# Arduino_UART_SIDEWAYS.net
KiCad netlist of a schematic drawn in EAGLE
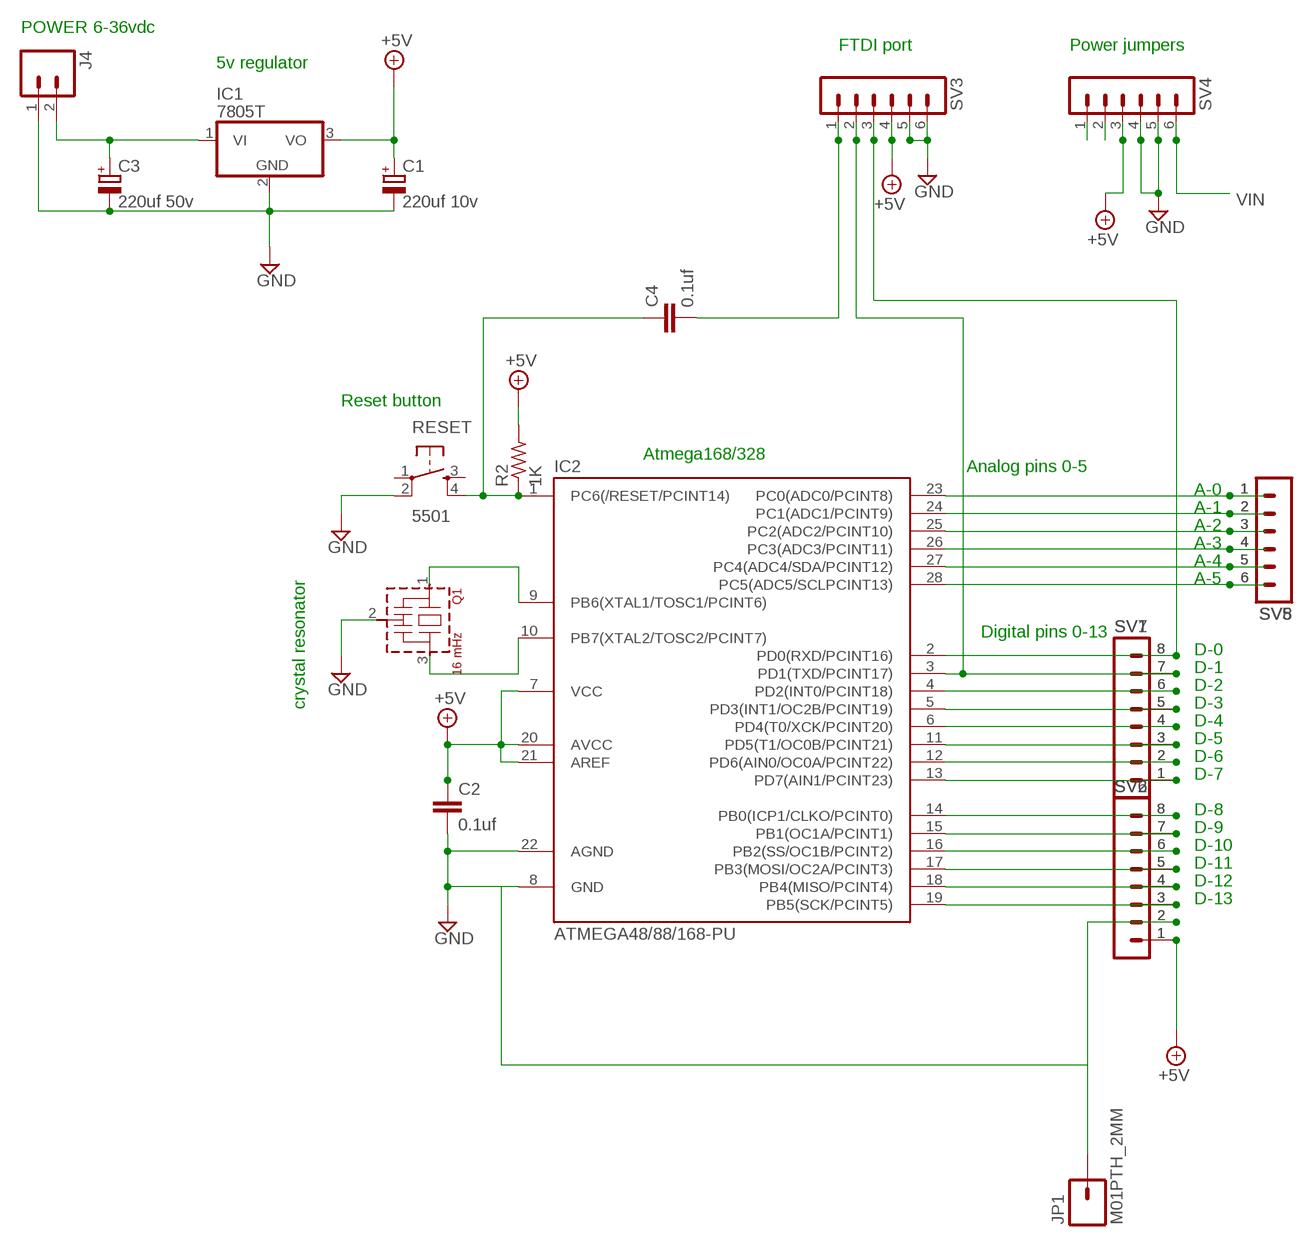
[diagram p0: schematic, sheet 1]

(export (version "E")
  (design (tool "Eeschema 10.0.6"))
  (components
    (comp (ref "C1")
      (value "220uf 10v")
      (footprint "eagle-import:E2,5-6")
      (libsource (lib "eagle-import") (part "CPOL-EUE2.5-6"))
    )
    (comp (ref "C2")
      (value "0.1uf")
      (footprint "eagle-import:C050-024X044")
      (libsource (lib "eagle-import") (part "C-EU050-024X044"))
    )
    (comp (ref "C3")
      (value "220uf 50v")
      (footprint "eagle-import:E2,5-6")
      (libsource (lib "eagle-import") (part "CPOL-EUE2.5-6"))
    )
    (comp (ref "C4")
      (value "0.1uf")
      (footprint "eagle-import:C075-032X103")
      (libsource (lib "eagle-import") (part "C-EU075-032X103"))
    )
    (comp (ref "IC1")
      (value "7805T")
      (footprint "eagle-import:TO220H")
      (libsource (lib "eagle-import") (part "78T05"))
    )
    (comp (ref "IC2")
      (value "ATMEGA48/88/168-PU")
      (footprint "eagle-import:DIL28-3")
      (libsource (lib "eagle-import") (part "ATMEGA48/88/168-PU"))
    )
    (comp (ref "J4")
      (value "M02LOCK")
      (footprint "eagle-import:1X02_LOCK")
      (libsource (lib "eagle-import") (part "M02LOCK"))
    )
    (comp (ref "JP1")
      (value "M01PTH_2MM")
      (footprint "eagle-import:1X01_2MM")
      (libsource (lib "eagle-import") (part "M01PTH_2MM"))
    )
    (comp (ref "Q1")
      (value "16 mHz")
      (footprint "eagle-import:CSTLS_X")
      (libsource (lib "eagle-import") (part "CSTLS_X"))
    )
    (comp (ref "R2")
      (value "1K")
      (footprint "eagle-import:0204_7")
      (libsource (lib "eagle-import") (part "R-US_0204/7"))
    )
    (comp (ref "RESET")
      (value "5501")
      (footprint "eagle-import:TACTILE-PTH")
      (libsource (lib "eagle-import") (part "TAC_SWITCHPTH"))
    )
    (comp (ref "SV1")
      (value "MA08-1")
      (footprint "eagle-import:MA08-1")
      (libsource (lib "eagle-import") (part "MA08-1"))
    )
    (comp (ref "SV2")
      (value "MA08-1")
      (footprint "eagle-import:MA08-1")
      (libsource (lib "eagle-import") (part "MA08-1"))
    )
    (comp (ref "SV3")
      (value "MA06-1")
      (footprint "eagle-import:MA06-1")
      (libsource (lib "eagle-import") (part "MA06-1"))
    )
    (comp (ref "SV4")
      (value "MA06-1")
      (footprint "eagle-import:MA06-1")
      (libsource (lib "eagle-import") (part "MA06-1"))
    )
    (comp (ref "SV5")
      (value "MA06-1")
      (footprint "eagle-import:MA06-1")
      (libsource (lib "eagle-import") (part "MA06-1"))
    )
    (comp (ref "SV6")
      (value "MA08-1")
      (footprint "eagle-import:MA08-1")
      (libsource (lib "eagle-import") (part "MA08-1"))
    )
    (comp (ref "SV7")
      (value "MA08-1")
      (footprint "eagle-import:MA08-1")
      (libsource (lib "eagle-import") (part "MA08-1"))
    )
    (comp (ref "SV8")
      (value "MA06-1")
      (footprint "eagle-import:MA06-1")
      (libsource (lib "eagle-import") (part "MA06-1"))
    )
  )
  (nets
    (net (code "1") (name "+5V") (class "Default")
      (node (ref "C1") (pin "+") (pinfunction "+_+") (pintype "passive"))
      (node (ref "C2") (pin "1") (pinfunction "1_1") (pintype "passive"))
      (node (ref "IC1") (pin "3") (pinfunction "VO_3") (pintype "passive"))
      (node (ref "IC2") (pin "20") (pinfunction "AVCC_20") (pintype "passive"))
      (node (ref "IC2") (pin "21") (pinfunction "AREF_21") (pintype "passive"))
      (node (ref "IC2") (pin "7") (pinfunction "VCC_7") (pintype "power_in"))
      (node (ref "R2") (pin "2") (pinfunction "2_2") (pintype "passive"))
      (node (ref "SV2") (pin "1") (pinfunction "1_1") (pintype "passive"))
      (node (ref "SV3") (pin "4") (pinfunction "4_4") (pintype "passive"))
      (node (ref "SV4") (pin "3") (pinfunction "3_3") (pintype "passive"))
      (node (ref "SV6") (pin "1") (pinfunction "1_1") (pintype "passive"))
    )
    (net (code "2") (name "/VIN") (class "Default")
      (node (ref "C3") (pin "+") (pinfunction "+_+") (pintype "passive"))
      (node (ref "IC1") (pin "1") (pinfunction "VI_1") (pintype "input"))
      (node (ref "J4") (pin "2") (pinfunction "2_2") (pintype "passive"))
      (node (ref "SV4") (pin "6") (pinfunction "6_6") (pintype "passive"))
    )
    (net (code "3") (name "GND") (class "Default")
      (node (ref "C1") (pin "-") (pinfunction "-_-") (pintype "passive"))
      (node (ref "C2") (pin "2") (pinfunction "2_2") (pintype "passive"))
      (node (ref "C3") (pin "-") (pinfunction "-_-") (pintype "passive"))
      (node (ref "IC1") (pin "2") (pinfunction "GND_2") (pintype "passive"))
      (node (ref "IC2") (pin "22") (pinfunction "AGND_22") (pintype "power_in"))
      (node (ref "IC2") (pin "8") (pinfunction "GND_8") (pintype "power_in"))
      (node (ref "J4") (pin "1") (pinfunction "1_1") (pintype "passive"))
      (node (ref "JP1") (pin "1") (pinfunction "1_1") (pintype "passive"))
      (node (ref "Q1") (pin "2") (pinfunction "VSS_2") (pintype "power_in"))
      (node (ref "RESET") (pin "2") (pinfunction "2_2") (pintype "passive"))
      (node (ref "SV2") (pin "2") (pinfunction "2_2") (pintype "passive"))
      (node (ref "SV3") (pin "5") (pinfunction "5_5") (pintype "passive"))
      (node (ref "SV3") (pin "6") (pinfunction "6_6") (pintype "passive"))
      (node (ref "SV4") (pin "4") (pinfunction "4_4") (pintype "passive"))
      (node (ref "SV4") (pin "5") (pinfunction "5_5") (pintype "passive"))
      (node (ref "SV6") (pin "2") (pinfunction "2_2") (pintype "passive"))
    )
    (net (code "4") (name "Net-(C4-Pad2)") (class "Default")
      (node (ref "C4") (pin "2") (pinfunction "2_2") (pintype "passive"))
      (node (ref "SV3") (pin "1") (pinfunction "1_1") (pintype "passive"))
    )
    (net (code "5") (name "Net-(IC2-PB0(ICP1{slash}CLKO{slash}PCINT0))") (class "Default")
      (node (ref "IC2") (pin "14") (pinfunction "PB0(ICP1/CLKO/PCINT0)_14") (pintype "bidirectional"))
      (node (ref "SV2") (pin "8") (pinfunction "8_8") (pintype "passive"))
      (node (ref "SV6") (pin "8") (pinfunction "8_8") (pintype "passive"))
    )
    (net (code "6") (name "Net-(IC2-PB1(OC1A{slash}PCINT1))") (class "Default")
      (node (ref "IC2") (pin "15") (pinfunction "PB1(OC1A/PCINT1)_15") (pintype "bidirectional"))
      (node (ref "SV2") (pin "7") (pinfunction "7_7") (pintype "passive"))
      (node (ref "SV6") (pin "7") (pinfunction "7_7") (pintype "passive"))
    )
    (net (code "7") (name "Net-(IC2-PB2(SS{slash}OC1B{slash}PCINT2))") (class "Default")
      (node (ref "IC2") (pin "16") (pinfunction "PB2(SS/OC1B/PCINT2)_16") (pintype "bidirectional"))
      (node (ref "SV2") (pin "6") (pinfunction "6_6") (pintype "passive"))
      (node (ref "SV6") (pin "6") (pinfunction "6_6") (pintype "passive"))
    )
    (net (code "8") (name "Net-(IC2-PB3(MOSI{slash}OC2A{slash}PCINT3))") (class "Default")
      (node (ref "IC2") (pin "17") (pinfunction "PB3(MOSI/OC2A/PCINT3)_17") (pintype "bidirectional"))
      (node (ref "SV2") (pin "5") (pinfunction "5_5") (pintype "passive"))
      (node (ref "SV6") (pin "5") (pinfunction "5_5") (pintype "passive"))
    )
    (net (code "9") (name "Net-(IC2-PB4(MISO{slash}PCINT4))") (class "Default")
      (node (ref "IC2") (pin "18") (pinfunction "PB4(MISO/PCINT4)_18") (pintype "bidirectional"))
      (node (ref "SV2") (pin "4") (pinfunction "4_4") (pintype "passive"))
      (node (ref "SV6") (pin "4") (pinfunction "4_4") (pintype "passive"))
    )
    (net (code "10") (name "Net-(IC2-PB5(SCK{slash}PCINT5))") (class "Default")
      (node (ref "IC2") (pin "19") (pinfunction "PB5(SCK/PCINT5)_19") (pintype "bidirectional"))
      (node (ref "SV2") (pin "3") (pinfunction "3_3") (pintype "passive"))
      (node (ref "SV6") (pin "3") (pinfunction "3_3") (pintype "passive"))
    )
    (net (code "11") (name "Net-(IC2-PB6(XTAL1{slash}TOSC1{slash}PCINT6))") (class "Default")
      (node (ref "IC2") (pin "9") (pinfunction "PB6(XTAL1/TOSC1/PCINT6)_9") (pintype "bidirectional"))
      (node (ref "Q1") (pin "1") (pinfunction "1_1") (pintype "output"))
    )
    (net (code "12") (name "Net-(IC2-PB7(XTAL2{slash}TOSC2{slash}PCINT7))") (class "Default")
      (node (ref "IC2") (pin "10") (pinfunction "PB7(XTAL2/TOSC2/PCINT7)_10") (pintype "bidirectional"))
      (node (ref "Q1") (pin "3") (pinfunction "3_3") (pintype "input"))
    )
    (net (code "13") (name "Net-(IC2-PC0(ADC0{slash}PCINT8))") (class "Default")
      (node (ref "IC2") (pin "23") (pinfunction "PC0(ADC0/PCINT8)_23") (pintype "bidirectional"))
      (node (ref "SV5") (pin "1") (pinfunction "1_1") (pintype "passive"))
      (node (ref "SV8") (pin "1") (pinfunction "1_1") (pintype "passive"))
    )
    (net (code "14") (name "Net-(IC2-PC1(ADC1{slash}PCINT9))") (class "Default")
      (node (ref "IC2") (pin "24") (pinfunction "PC1(ADC1/PCINT9)_24") (pintype "bidirectional"))
      (node (ref "SV5") (pin "2") (pinfunction "2_2") (pintype "passive"))
      (node (ref "SV8") (pin "2") (pinfunction "2_2") (pintype "passive"))
    )
    (net (code "15") (name "Net-(IC2-PC2(ADC2{slash}PCINT10))") (class "Default")
      (node (ref "IC2") (pin "25") (pinfunction "PC2(ADC2/PCINT10)_25") (pintype "bidirectional"))
      (node (ref "SV5") (pin "3") (pinfunction "3_3") (pintype "passive"))
      (node (ref "SV8") (pin "3") (pinfunction "3_3") (pintype "passive"))
    )
    (net (code "16") (name "Net-(IC2-PC3(ADC3{slash}PCINT11))") (class "Default")
      (node (ref "IC2") (pin "26") (pinfunction "PC3(ADC3/PCINT11)_26") (pintype "bidirectional"))
      (node (ref "SV5") (pin "4") (pinfunction "4_4") (pintype "passive"))
      (node (ref "SV8") (pin "4") (pinfunction "4_4") (pintype "passive"))
    )
    (net (code "17") (name "Net-(IC2-PC4(ADC4{slash}SDA{slash}PCINT12))") (class "Default")
      (node (ref "IC2") (pin "27") (pinfunction "PC4(ADC4/SDA/PCINT12)_27") (pintype "bidirectional"))
      (node (ref "SV5") (pin "5") (pinfunction "5_5") (pintype "passive"))
      (node (ref "SV8") (pin "5") (pinfunction "5_5") (pintype "passive"))
    )
    (net (code "18") (name "Net-(IC2-PC5(ADC5{slash}SCLPCINT13))") (class "Default")
      (node (ref "IC2") (pin "28") (pinfunction "PC5(ADC5/SCLPCINT13)_28") (pintype "bidirectional"))
      (node (ref "SV5") (pin "6") (pinfunction "6_6") (pintype "passive"))
      (node (ref "SV8") (pin "6") (pinfunction "6_6") (pintype "passive"))
    )
    (net (code "19") (name "Net-(IC2-PC6({slash}RESET{slash}PCINT14))") (class "Default")
      (node (ref "C4") (pin "1") (pinfunction "1_1") (pintype "passive"))
      (node (ref "IC2") (pin "1") (pinfunction "PC6(/RESET/PCINT14)_1") (pintype "bidirectional"))
      (node (ref "R2") (pin "1") (pinfunction "1_1") (pintype "passive"))
      (node (ref "RESET") (pin "4") (pinfunction "4_4") (pintype "passive"))
    )
    (net (code "20") (name "Net-(IC2-PD0(RXD{slash}PCINT16))") (class "Default")
      (node (ref "IC2") (pin "2") (pinfunction "PD0(RXD/PCINT16)_2") (pintype "bidirectional"))
      (node (ref "SV1") (pin "8") (pinfunction "8_8") (pintype "passive"))
      (node (ref "SV3") (pin "3") (pinfunction "3_3") (pintype "passive"))
      (node (ref "SV7") (pin "8") (pinfunction "8_8") (pintype "passive"))
    )
    (net (code "21") (name "Net-(IC2-PD1(TXD{slash}PCINT17))") (class "Default")
      (node (ref "IC2") (pin "3") (pinfunction "PD1(TXD/PCINT17)_3") (pintype "bidirectional"))
      (node (ref "SV1") (pin "7") (pinfunction "7_7") (pintype "passive"))
      (node (ref "SV3") (pin "2") (pinfunction "2_2") (pintype "passive"))
      (node (ref "SV7") (pin "7") (pinfunction "7_7") (pintype "passive"))
    )
    (net (code "22") (name "Net-(IC2-PD2(INT0{slash}PCINT18))") (class "Default")
      (node (ref "IC2") (pin "4") (pinfunction "PD2(INT0/PCINT18)_4") (pintype "bidirectional"))
      (node (ref "SV1") (pin "6") (pinfunction "6_6") (pintype "passive"))
      (node (ref "SV7") (pin "6") (pinfunction "6_6") (pintype "passive"))
    )
    (net (code "23") (name "Net-(IC2-PD3(INT1{slash}OC2B{slash}PCINT19))") (class "Default")
      (node (ref "IC2") (pin "5") (pinfunction "PD3(INT1/OC2B/PCINT19)_5") (pintype "bidirectional"))
      (node (ref "SV1") (pin "5") (pinfunction "5_5") (pintype "passive"))
      (node (ref "SV7") (pin "5") (pinfunction "5_5") (pintype "passive"))
    )
    (net (code "24") (name "Net-(IC2-PD4(T0{slash}XCK{slash}PCINT20))") (class "Default")
      (node (ref "IC2") (pin "6") (pinfunction "PD4(T0/XCK/PCINT20)_6") (pintype "bidirectional"))
      (node (ref "SV1") (pin "4") (pinfunction "4_4") (pintype "passive"))
      (node (ref "SV7") (pin "4") (pinfunction "4_4") (pintype "passive"))
    )
    (net (code "25") (name "Net-(IC2-PD5(T1{slash}OC0B{slash}PCINT21))") (class "Default")
      (node (ref "IC2") (pin "11") (pinfunction "PD5(T1/OC0B/PCINT21)_11") (pintype "bidirectional"))
      (node (ref "SV1") (pin "3") (pinfunction "3_3") (pintype "passive"))
      (node (ref "SV7") (pin "3") (pinfunction "3_3") (pintype "passive"))
    )
    (net (code "26") (name "Net-(IC2-PD6(AIN0{slash}OC0A{slash}PCINT22))") (class "Default")
      (node (ref "IC2") (pin "12") (pinfunction "PD6(AIN0/OC0A/PCINT22)_12") (pintype "bidirectional"))
      (node (ref "SV1") (pin "2") (pinfunction "2_2") (pintype "passive"))
      (node (ref "SV7") (pin "2") (pinfunction "2_2") (pintype "passive"))
    )
    (net (code "27") (name "Net-(IC2-PD7(AIN1{slash}PCINT23))") (class "Default")
      (node (ref "IC2") (pin "13") (pinfunction "PD7(AIN1/PCINT23)_13") (pintype "bidirectional"))
      (node (ref "SV1") (pin "1") (pinfunction "1_1") (pintype "passive"))
      (node (ref "SV7") (pin "1") (pinfunction "1_1") (pintype "passive"))
    )
    (net (code "28") (name "unconnected-(RESET-Pad1)") (class "Default")
      (node (ref "RESET") (pin "1") (pinfunction "1_1") (pintype "passive"))
    )
    (net (code "29") (name "unconnected-(RESET-Pad3)") (class "Default")
      (node (ref "RESET") (pin "3") (pinfunction "3_3") (pintype "passive"))
    )
    (net (code "30") (name "unconnected-(SV4-Pad1)") (class "Default")
      (node (ref "SV4") (pin "1") (pinfunction "1_1") (pintype "passive"))
    )
    (net (code "31") (name "unconnected-(SV4-Pad2)") (class "Default")
      (node (ref "SV4") (pin "2") (pinfunction "2_2") (pintype "passive"))
    )
  )
)
